# ZemoteShield.net
KiCad netlist of a schematic drawn in EAGLE
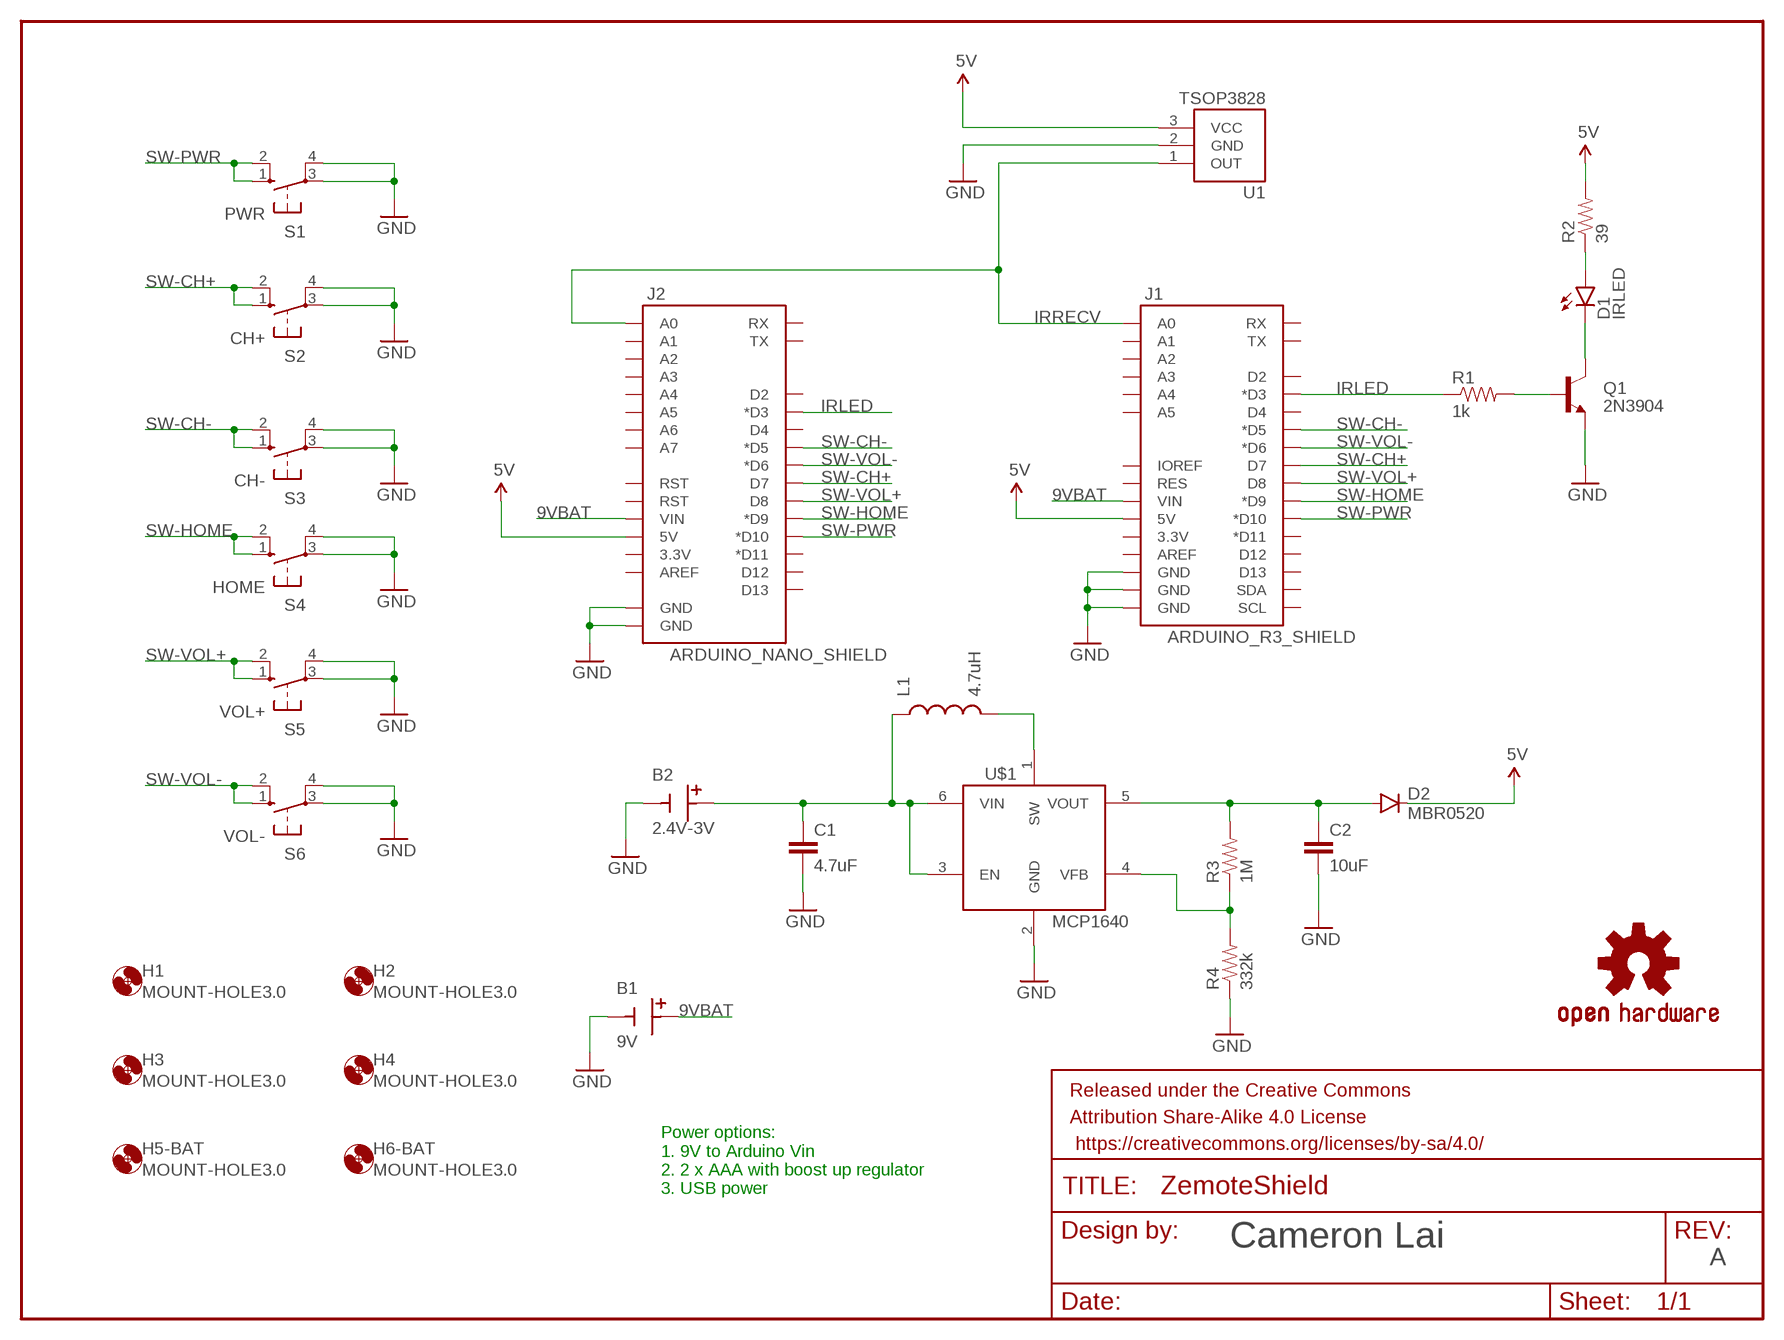
[diagram p0: schematic, sheet 1]

(export (version "E")
  (design (tool "Eeschema 10.0.6"))
  (components
    (comp (ref "B1")
      (value "9V")
      (footprint "eagle-import:BATTERY-2PIN-CON")
      (libsource (lib "eagle-import") (part "BATTERY-HOLES"))
    )
    (comp (ref "B2")
      (value "2.4V-3V")
      (footprint "eagle-import:BATTERY-2PIN-CON")
      (libsource (lib "eagle-import") (part "BATTERY-HOLES"))
    )
    (comp (ref "C1")
      (value "4.7uF")
      (footprint "eagle-import:0603-CAP")
      (libsource (lib "eagle-import") (part "4.7UF-6.3V-10%(0603)0603"))
    )
    (comp (ref "C2")
      (value "10uF")
      (footprint "eagle-import:0805")
      (libsource (lib "eagle-import") (part "CAP0805"))
    )
    (comp (ref "D1")
      (value "IRLED")
      (footprint "eagle-import:LED5MM")
      (libsource (lib "eagle-import") (part "LED5MM"))
    )
    (comp (ref "D2")
      (value "MBR0520")
      (footprint "eagle-import:SOD-123")
      (libsource (lib "eagle-import") (part "DIODESOD123"))
    )
    (comp (ref "FRAME1")
      (value "ZemoteShield")
      (footprint "eagle-import:DUMMY")
      (fields
        (field (name "DESIGNER") "Nobody")
        (field (name "VERSION") "v01")
        (field (name "DESIGNER_1") "Cameron Lai")
        (field (name "VERSION_1") "A")
      )
      (libsource (lib "eagle-import") (part "FRAME-LETTERNO_PACKAGE"))
    )
    (comp (ref "H1")
      (value "MOUNT-HOLE3.0")
      (footprint "eagle-import:3,0")
      (libsource (lib "eagle-import") (part "MOUNT-HOLE3.0"))
    )
    (comp (ref "H2")
      (value "MOUNT-HOLE3.0")
      (footprint "eagle-import:3,0")
      (libsource (lib "eagle-import") (part "MOUNT-HOLE3.0"))
    )
    (comp (ref "H3")
      (value "MOUNT-HOLE3.0")
      (footprint "eagle-import:3,0")
      (libsource (lib "eagle-import") (part "MOUNT-HOLE3.0"))
    )
    (comp (ref "H4")
      (value "MOUNT-HOLE3.0")
      (footprint "eagle-import:3,0")
      (libsource (lib "eagle-import") (part "MOUNT-HOLE3.0"))
    )
    (comp (ref "H5-BAT")
      (value "MOUNT-HOLE3.0")
      (footprint "eagle-import:3,0")
      (libsource (lib "eagle-import") (part "MOUNT-HOLE3.0"))
    )
    (comp (ref "H6-BAT")
      (value "MOUNT-HOLE3.0")
      (footprint "eagle-import:3,0")
      (libsource (lib "eagle-import") (part "MOUNT-HOLE3.0"))
    )
    (comp (ref "J1")
      (value "ARDUINO_R3_SHIELD")
      (footprint "eagle-import:UNO_R3_SHIELD")
      (libsource (lib "eagle-import") (part "ARDUINO_R3_SHIELD"))
    )
    (comp (ref "J2")
      (value "ARDUINO_NANO_SHIELD")
      (footprint "eagle-import:NANO_SHIELD")
      (libsource (lib "eagle-import") (part "ARDUINO_NANO_SHIELD"))
    )
    (comp (ref "L1")
      (value "4.7uH")
      (footprint "eagle-import:1210")
      (libsource (lib "eagle-import") (part "INDUCTOR1210"))
    )
    (comp (ref "LOGO1")
      (value "OSHW-LOGOL")
      (footprint "eagle-import:OSHW-LOGO-L")
      (libsource (lib "eagle-import") (part "OSHW-LOGOL"))
    )
    (comp (ref "Q1")
      (value "2N3904")
      (footprint "eagle-import:TO-92")
      (libsource (lib "eagle-import") (part "TRANSISTOR_NPN2N3904"))
    )
    (comp (ref "R1")
      (value "1k")
      (footprint "eagle-import:AXIAL-0.4")
      (libsource (lib "eagle-import") (part "RESISTORPTH-1/4W"))
    )
    (comp (ref "R2")
      (value "39")
      (footprint "eagle-import:AXIAL-0.6")
      (libsource (lib "eagle-import") (part "RESISTORPTH-1W"))
    )
    (comp (ref "R3")
      (value "1M")
      (footprint "eagle-import:0603-RES")
      (libsource (lib "eagle-import") (part "RESISTOR0603"))
    )
    (comp (ref "R4")
      (value "332k")
      (footprint "eagle-import:0603-RES")
      (libsource (lib "eagle-import") (part "RESISTOR0603"))
    )
    (comp (ref "S1")
      (value "PWR")
      (footprint "eagle-import:B3F-10XX")
      (fields (field (name "MPN") "B3F-1000"))
      (libsource (lib "eagle-import") (part "10-XX"))
    )
    (comp (ref "S2")
      (value "CH+")
      (footprint "eagle-import:B3F-10XX")
      (fields (field (name "MPN") "B3F-1000"))
      (libsource (lib "eagle-import") (part "10-XX"))
    )
    (comp (ref "S3")
      (value "CH-")
      (footprint "eagle-import:B3F-10XX")
      (fields (field (name "MPN") "B3F-1000"))
      (libsource (lib "eagle-import") (part "10-XX"))
    )
    (comp (ref "S4")
      (value "HOME")
      (footprint "eagle-import:B3F-10XX")
      (fields (field (name "MPN") "B3F-1000"))
      (libsource (lib "eagle-import") (part "10-XX"))
    )
    (comp (ref "S5")
      (value "VOL+")
      (footprint "eagle-import:B3F-10XX")
      (fields (field (name "MPN") "B3F-1000"))
      (libsource (lib "eagle-import") (part "10-XX"))
    )
    (comp (ref "S6")
      (value "VOL-")
      (footprint "eagle-import:B3F-10XX")
      (fields (field (name "MPN") "B3F-1000"))
      (libsource (lib "eagle-import") (part "10-XX"))
    )
    (comp (ref "U$1")
      (value "MCP1640")
      (footprint "eagle-import:SOT23-6")
      (libsource (lib "eagle-import") (part "MCP1640"))
    )
    (comp (ref "U1")
      (value "TSOP3828")
      (footprint "eagle-import:BRM-2508")
      (libsource (lib "eagle-import") (part "BRM-2A18RA"))
    )
  )
  (nets
    (net (code "1") (name "/9VBAT") (class "Default")
      (node (ref "B1") (pin "POS") (pinfunction "POS_POS") (pintype "passive"))
      (node (ref "J1") (pin "VIN") (pinfunction "VIN_VIN") (pintype "bidirectional"))
      (node (ref "J2") (pin "VIN") (pinfunction "VIN_VIN") (pintype "bidirectional"))
    )
    (net (code "2") (name "/IRLED") (class "Default")
      (node (ref "J1") (pin "D3") (pinfunction "*D3_D3") (pintype "bidirectional"))
      (node (ref "J2") (pin "D3") (pinfunction "*D3_D3") (pintype "bidirectional"))
      (node (ref "R1") (pin "P$1") (pinfunction "1_P$1") (pintype "passive"))
    )
    (net (code "3") (name "/IRRECV") (class "Default")
      (node (ref "J1") (pin "A0") (pinfunction "A0_A0") (pintype "bidirectional"))
      (node (ref "J2") (pin "A0") (pinfunction "A0_A0") (pintype "bidirectional"))
      (node (ref "U1") (pin "1") (pinfunction "OUT_1") (pintype "bidirectional"))
    )
    (net (code "4") (name "/SW-CH+") (class "Default")
      (node (ref "J1") (pin "D7") (pinfunction "D7_D7") (pintype "bidirectional"))
      (node (ref "J2") (pin "D7") (pinfunction "D7_D7") (pintype "bidirectional"))
      (node (ref "S2") (pin "1") (pinfunction "S_1") (pintype "passive"))
      (node (ref "S2") (pin "2") (pinfunction "S1_2") (pintype "passive"))
    )
    (net (code "5") (name "/SW-CH-") (class "Default")
      (node (ref "J1") (pin "D5") (pinfunction "*D5_D5") (pintype "bidirectional"))
      (node (ref "J2") (pin "D5") (pinfunction "*D5_D5") (pintype "bidirectional"))
      (node (ref "S3") (pin "1") (pinfunction "S_1") (pintype "passive"))
      (node (ref "S3") (pin "2") (pinfunction "S1_2") (pintype "passive"))
    )
    (net (code "6") (name "/SW-HOME") (class "Default")
      (node (ref "J1") (pin "D9") (pinfunction "*D9_D9") (pintype "bidirectional"))
      (node (ref "J2") (pin "D9") (pinfunction "*D9_D9") (pintype "bidirectional"))
      (node (ref "S4") (pin "1") (pinfunction "S_1") (pintype "passive"))
      (node (ref "S4") (pin "2") (pinfunction "S1_2") (pintype "passive"))
    )
    (net (code "7") (name "/SW-PWR") (class "Default")
      (node (ref "J1") (pin "D10") (pinfunction "*D10_D10") (pintype "bidirectional"))
      (node (ref "J2") (pin "D10") (pinfunction "*D10_D10") (pintype "bidirectional"))
      (node (ref "S1") (pin "1") (pinfunction "S_1") (pintype "passive"))
      (node (ref "S1") (pin "2") (pinfunction "S1_2") (pintype "passive"))
    )
    (net (code "8") (name "/SW-VOL+") (class "Default")
      (node (ref "J1") (pin "D8") (pinfunction "D8_D8") (pintype "bidirectional"))
      (node (ref "J2") (pin "D8") (pinfunction "D8_D8") (pintype "bidirectional"))
      (node (ref "S5") (pin "1") (pinfunction "S_1") (pintype "passive"))
      (node (ref "S5") (pin "2") (pinfunction "S1_2") (pintype "passive"))
    )
    (net (code "9") (name "/SW-VOL-") (class "Default")
      (node (ref "J1") (pin "D6") (pinfunction "*D6_D6") (pintype "bidirectional"))
      (node (ref "J2") (pin "D6") (pinfunction "*D6_D6") (pintype "bidirectional"))
      (node (ref "S6") (pin "1") (pinfunction "S_1") (pintype "passive"))
      (node (ref "S6") (pin "2") (pinfunction "S1_2") (pintype "passive"))
    )
    (net (code "10") (name "5V") (class "Default")
      (node (ref "D2") (pin "C") (pinfunction "C_C") (pintype "passive"))
      (node (ref "J1") (pin "5V") (pinfunction "5V_5V") (pintype "bidirectional"))
      (node (ref "J2") (pin "5V") (pinfunction "5V_5V") (pintype "bidirectional"))
      (node (ref "R2") (pin "P$2") (pinfunction "2_P$2") (pintype "passive"))
      (node (ref "U1") (pin "3") (pinfunction "VCC_3") (pintype "bidirectional"))
    )
    (net (code "11") (name "GND") (class "Default")
      (node (ref "B1") (pin "NEG") (pinfunction "NEG_NEG") (pintype "passive"))
      (node (ref "B2") (pin "NEG") (pinfunction "NEG_NEG") (pintype "passive"))
      (node (ref "C1") (pin "2") (pinfunction "2_2") (pintype "passive"))
      (node (ref "C2") (pin "2") (pinfunction "2_2") (pintype "passive"))
      (node (ref "J1") (pin "GND@0") (pinfunction "GND_GND@0") (pintype "bidirectional"))
      (node (ref "J1") (pin "GND@1") (pinfunction "GND_GND@1") (pintype "bidirectional"))
      (node (ref "J1") (pin "GND@2") (pinfunction "GND_GND@2") (pintype "bidirectional"))
      (node (ref "J2") (pin "GND@0") (pinfunction "GND_GND@0") (pintype "bidirectional"))
      (node (ref "J2") (pin "GND@1") (pinfunction "GND_GND@1") (pintype "bidirectional"))
      (node (ref "Q1") (pin "1") (pinfunction "E_1") (pintype "passive"))
      (node (ref "R4") (pin "1") (pinfunction "1_1") (pintype "passive"))
      (node (ref "S1") (pin "3") (pinfunction "P_3") (pintype "passive"))
      (node (ref "S1") (pin "4") (pinfunction "P1_4") (pintype "passive"))
      (node (ref "S2") (pin "3") (pinfunction "P_3") (pintype "passive"))
      (node (ref "S2") (pin "4") (pinfunction "P1_4") (pintype "passive"))
      (node (ref "S3") (pin "3") (pinfunction "P_3") (pintype "passive"))
      (node (ref "S3") (pin "4") (pinfunction "P1_4") (pintype "passive"))
      (node (ref "S4") (pin "3") (pinfunction "P_3") (pintype "passive"))
      (node (ref "S4") (pin "4") (pinfunction "P1_4") (pintype "passive"))
      (node (ref "S5") (pin "3") (pinfunction "P_3") (pintype "passive"))
      (node (ref "S5") (pin "4") (pinfunction "P1_4") (pintype "passive"))
      (node (ref "S6") (pin "3") (pinfunction "P_3") (pintype "passive"))
      (node (ref "S6") (pin "4") (pinfunction "P1_4") (pintype "passive"))
      (node (ref "U$1") (pin "2") (pinfunction "GND_2") (pintype "power_in"))
      (node (ref "U1") (pin "2") (pinfunction "GND_2") (pintype "bidirectional"))
    )
    (net (code "12") (name "Net-(D1-C)") (class "Default")
      (node (ref "D1") (pin "K") (pinfunction "C_K") (pintype "passive"))
      (node (ref "Q1") (pin "3") (pinfunction "C_3") (pintype "passive"))
    )
    (net (code "13") (name "Net-(Q1-B)") (class "Default")
      (node (ref "Q1") (pin "2") (pinfunction "B_2") (pintype "passive"))
      (node (ref "R1") (pin "P$2") (pinfunction "2_P$2") (pintype "passive"))
    )
    (net (code "14") (name "Net-(R2-1)") (class "Default")
      (node (ref "D1") (pin "A") (pinfunction "A_A") (pintype "passive"))
      (node (ref "R2") (pin "P$1") (pinfunction "1_P$1") (pintype "passive"))
    )
    (net (code "15") (name "Net-(U$1-EN)") (class "Default")
      (node (ref "B2") (pin "POS") (pinfunction "POS_POS") (pintype "passive"))
      (node (ref "C1") (pin "1") (pinfunction "1_1") (pintype "passive"))
      (node (ref "L1") (pin "1") (pinfunction "1_1") (pintype "passive"))
      (node (ref "U$1") (pin "3") (pinfunction "EN_3") (pintype "input"))
      (node (ref "U$1") (pin "6") (pinfunction "VIN_6") (pintype "power_in"))
    )
    (net (code "16") (name "Net-(U$1-SW)") (class "Default")
      (node (ref "L1") (pin "2") (pinfunction "2_2") (pintype "passive"))
      (node (ref "U$1") (pin "1") (pinfunction "SW_1") (pintype "passive"))
    )
    (net (code "17") (name "Net-(U$1-VFB)") (class "Default")
      (node (ref "R3") (pin "1") (pinfunction "1_1") (pintype "passive"))
      (node (ref "R4") (pin "2") (pinfunction "2_2") (pintype "passive"))
      (node (ref "U$1") (pin "4") (pinfunction "VFB_4") (pintype "input"))
    )
    (net (code "18") (name "Net-(U$1-VOUT)") (class "Default")
      (node (ref "C2") (pin "1") (pinfunction "1_1") (pintype "passive"))
      (node (ref "D2") (pin "A") (pinfunction "A_A") (pintype "passive"))
      (node (ref "R3") (pin "2") (pinfunction "2_2") (pintype "passive"))
      (node (ref "U$1") (pin "5") (pinfunction "VOUT_5") (pintype "power_in"))
    )
    (net (code "19") (name "unconnected-(J1-*D11-PadD11)") (class "Default")
      (node (ref "J1") (pin "D11") (pinfunction "*D11_D11") (pintype "bidirectional"))
    )
    (net (code "20") (name "unconnected-(J1-Pad3.3V)") (class "Default")
      (node (ref "J1") (pin "3.3V") (pinfunction "3.3V_3.3V") (pintype "bidirectional"))
    )
    (net (code "21") (name "unconnected-(J1-PadA1)") (class "Default")
      (node (ref "J1") (pin "A1") (pinfunction "A1_A1") (pintype "bidirectional"))
    )
    (net (code "22") (name "unconnected-(J1-PadA2)") (class "Default")
      (node (ref "J1") (pin "A2") (pinfunction "A2_A2") (pintype "bidirectional"))
    )
    (net (code "23") (name "unconnected-(J1-PadA3)") (class "Default")
      (node (ref "J1") (pin "A3") (pinfunction "A3_A3") (pintype "bidirectional"))
    )
    (net (code "24") (name "unconnected-(J1-PadA4)") (class "Default")
      (node (ref "J1") (pin "A4") (pinfunction "A4_A4") (pintype "bidirectional"))
    )
    (net (code "25") (name "unconnected-(J1-PadA5)") (class "Default")
      (node (ref "J1") (pin "A5") (pinfunction "A5_A5") (pintype "bidirectional"))
    )
    (net (code "26") (name "unconnected-(J1-PadAREF)") (class "Default")
      (node (ref "J1") (pin "AREF") (pinfunction "AREF_AREF") (pintype "bidirectional"))
    )
    (net (code "27") (name "unconnected-(J1-PadD2)") (class "Default")
      (node (ref "J1") (pin "D2") (pinfunction "D2_D2") (pintype "bidirectional"))
    )
    (net (code "28") (name "unconnected-(J1-PadD4)") (class "Default")
      (node (ref "J1") (pin "D4") (pinfunction "D4_D4") (pintype "bidirectional"))
    )
    (net (code "29") (name "unconnected-(J1-PadD12)") (class "Default")
      (node (ref "J1") (pin "D12") (pinfunction "D12_D12") (pintype "bidirectional"))
    )
    (net (code "30") (name "unconnected-(J1-PadD13)") (class "Default")
      (node (ref "J1") (pin "D13") (pinfunction "D13_D13") (pintype "bidirectional"))
    )
    (net (code "31") (name "unconnected-(J1-PadIOREF)") (class "Default")
      (node (ref "J1") (pin "IOREF") (pinfunction "IOREF_IOREF") (pintype "bidirectional"))
    )
    (net (code "32") (name "unconnected-(J1-PadRES)") (class "Default")
      (node (ref "J1") (pin "RES") (pinfunction "RES_RES") (pintype "bidirectional"))
    )
    (net (code "33") (name "unconnected-(J1-PadRX)") (class "Default")
      (node (ref "J1") (pin "RX") (pinfunction "RX_RX") (pintype "bidirectional"))
    )
    (net (code "34") (name "unconnected-(J1-PadSCL)") (class "Default")
      (node (ref "J1") (pin "SCL") (pinfunction "SCL_SCL") (pintype "bidirectional"))
    )
    (net (code "35") (name "unconnected-(J1-PadSDA)") (class "Default")
      (node (ref "J1") (pin "SDA") (pinfunction "SDA_SDA") (pintype "bidirectional"))
    )
    (net (code "36") (name "unconnected-(J1-PadTX)") (class "Default")
      (node (ref "J1") (pin "TX") (pinfunction "TX_TX") (pintype "bidirectional"))
    )
    (net (code "37") (name "unconnected-(J2-*D11-PadD11)") (class "Default")
      (node (ref "J2") (pin "D11") (pinfunction "*D11_D11") (pintype "bidirectional"))
    )
    (net (code "38") (name "unconnected-(J2-Pad3.3V)") (class "Default")
      (node (ref "J2") (pin "3.3V") (pinfunction "3.3V_3.3V") (pintype "bidirectional"))
    )
    (net (code "39") (name "unconnected-(J2-PadA1)") (class "Default")
      (node (ref "J2") (pin "A1") (pinfunction "A1_A1") (pintype "bidirectional"))
    )
    (net (code "40") (name "unconnected-(J2-PadA2)") (class "Default")
      (node (ref "J2") (pin "A2") (pinfunction "A2_A2") (pintype "bidirectional"))
    )
    (net (code "41") (name "unconnected-(J2-PadA3)") (class "Default")
      (node (ref "J2") (pin "A3") (pinfunction "A3_A3") (pintype "bidirectional"))
    )
    (net (code "42") (name "unconnected-(J2-PadA4)") (class "Default")
      (node (ref "J2") (pin "A4") (pinfunction "A4_A4") (pintype "bidirectional"))
    )
    (net (code "43") (name "unconnected-(J2-PadA5)") (class "Default")
      (node (ref "J2") (pin "A5") (pinfunction "A5_A5") (pintype "bidirectional"))
    )
    (net (code "44") (name "unconnected-(J2-PadA6)") (class "Default")
      (node (ref "J2") (pin "A6") (pinfunction "A6_A6") (pintype "bidirectional"))
    )
    (net (code "45") (name "unconnected-(J2-PadA7)") (class "Default")
      (node (ref "J2") (pin "A7") (pinfunction "A7_A7") (pintype "bidirectional"))
    )
    (net (code "46") (name "unconnected-(J2-PadAREF)") (class "Default")
      (node (ref "J2") (pin "AREF") (pinfunction "AREF_AREF") (pintype "bidirectional"))
    )
    (net (code "47") (name "unconnected-(J2-PadD2)") (class "Default")
      (node (ref "J2") (pin "D2") (pinfunction "D2_D2") (pintype "bidirectional"))
    )
    (net (code "48") (name "unconnected-(J2-PadD4)") (class "Default")
      (node (ref "J2") (pin "D4") (pinfunction "D4_D4") (pintype "bidirectional"))
    )
    (net (code "49") (name "unconnected-(J2-PadD12)") (class "Default")
      (node (ref "J2") (pin "D12") (pinfunction "D12_D12") (pintype "bidirectional"))
    )
    (net (code "50") (name "unconnected-(J2-PadD13)") (class "Default")
      (node (ref "J2") (pin "D13") (pinfunction "D13_D13") (pintype "bidirectional"))
    )
    (net (code "51") (name "unconnected-(J2-PadRX)") (class "Default")
      (node (ref "J2") (pin "RX") (pinfunction "RX_RX") (pintype "bidirectional"))
    )
    (net (code "52") (name "unconnected-(J2-PadTX)") (class "Default")
      (node (ref "J2") (pin "TX") (pinfunction "TX_TX") (pintype "bidirectional"))
    )
    (net (code "53") (name "unconnected-(J2-RST-PadRST@0)") (class "Default")
      (node (ref "J2") (pin "RST@0") (pinfunction "RST_RST@0") (pintype "bidirectional"))
    )
    (net (code "54") (name "unconnected-(J2-RST-PadRST@1)") (class "Default")
      (node (ref "J2") (pin "RST@1") (pinfunction "RST_RST@1") (pintype "bidirectional"))
    )
  )
)
